# 20241126.net
KiCad netlist of a schematic drawn in Altium Designer
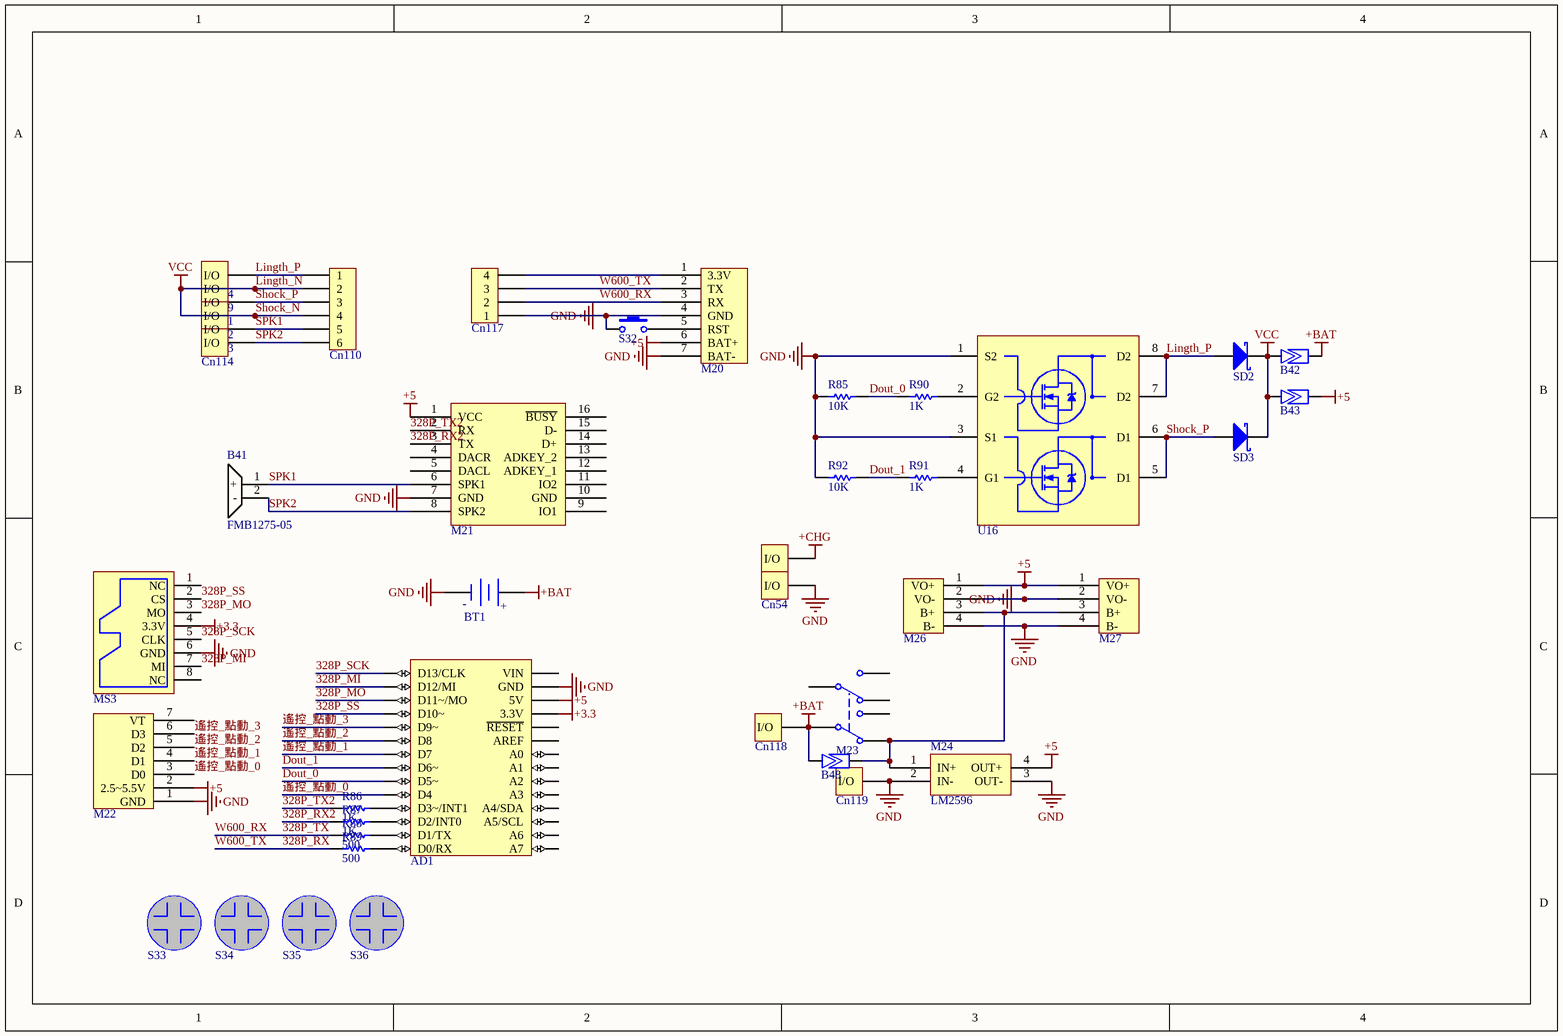
[diagram p0: 松菸_幻影光靈_屍禁_提燈_20241126.SchDoc]

(export (version "E")
  (design (tool "Eeschema 10.0.6"))
  (components
    (comp (ref "AD1")
      (value "Arduino NANO")
      (footprint "Arduino NANO")
      (description "單晶片")
      (libsource (lib "MyLibray") (part "Arduino NANO"))
    )
    (comp (ref "B41")
      (value "FMB1275-05")
      (footprint "Buzzer_12085")
      (description "無源蜂鳴器")
      (libsource (lib "MyLibray") (part "Buzzer"))
    )
    (comp (ref "B42")
      (value "短路")
      (footprint "BYPASS-0805")
      (description "短路焊點(如標註短路則需額外補錫使其短路)")
      (libsource (lib "MyLibray") (part "Bypass"))
    )
    (comp (ref "B43")
      (value "短路")
      (footprint "BYPASS-0805")
      (description "短路焊點(如標註短路則需額外補錫使其短路)")
      (libsource (lib "MyLibray") (part "Bypass"))
    )
    (comp (ref "B48")
      (value "短路")
      (footprint "BYPASS-1206")
      (description "短路焊點(如標註短路則需額外補錫使其短路)")
      (libsource (lib "MyLibray") (part "Bypass"))
    )
    (comp (ref "BT1")
      (value "18650")
      (footprint "Battery_18650")
      (description "電池")
      (libsource (lib "MyLibray") (part "Battery"))
    )
    (comp (ref "Cn53")
      (value "Contact")
      (footprint "Conntact_Stamp hole_0.6\"")
      (description "接線端子、接點、郵票孔(非焊接元件)")
      (libsource (lib "MyLibray") (part "Conntact"))
    )
    (comp (ref "Cn54")
      (value "Contact")
      (footprint "Conntact_Stamp hole_0.6\"")
      (description "接線端子、接點、郵票孔(非焊接元件)")
      (libsource (lib "MyLibray") (part "Conntact"))
    )
    (comp (ref "Cn104")
      (value "Contact")
      (footprint "Conntact_Stamp hole_0.6\"")
      (description "接線端子、接點、郵票孔(非焊接元件)")
      (libsource (lib "MyLibray") (part "Conntact"))
    )
    (comp (ref "Cn109")
      (value "Contact")
      (footprint "Conntact_Stamp hole_0.6\"")
      (description "接線端子、接點、郵票孔(非焊接元件)")
      (libsource (lib "") (part "Conntact_1"))
    )
    (comp (ref "Cn110")
      (value "KF2510-6")
      (footprint "Connector_KF2510-6A")
      (description "連接器")
      (libsource (lib "MyLibray") (part "Conntact(6P)"))
    )
    (comp (ref "Cn111")
      (value "Contact")
      (footprint "Conntact_Stamp hole_0.6\"")
      (description "接線端子、接點、郵票孔(非焊接元件)")
      (libsource (lib "MyLibray") (part "Conntact"))
    )
    (comp (ref "Cn112")
      (value "Contact")
      (footprint "Conntact_Stamp hole_0.6\"")
      (description "接線端子、接點、郵票孔(非焊接元件)")
      (libsource (lib "MyLibray") (part "Conntact"))
    )
    (comp (ref "Cn113")
      (value "Contact")
      (footprint "Conntact_Stamp hole_0.6\"")
      (description "接線端子、接點、郵票孔(非焊接元件)")
      (libsource (lib "MyLibray") (part "Conntact"))
    )
    (comp (ref "Cn114")
      (value "Contact")
      (footprint "Conntact_Stamp hole_0.6\"")
      (description "接線端子、接點、郵票孔(非焊接元件)")
      (libsource (lib "MyLibray") (part "Conntact"))
    )
    (comp (ref "Cn117")
      (value "KF2510-4")
      (footprint "Connector_KF2510-4A")
      (description "連接器")
      (libsource (lib "MyLibray") (part "Conntact(4P)"))
    )
    (comp (ref "Cn118")
      (value "Contact")
      (footprint "Conntact_Stamp hole_0.6\"")
      (description "接線端子、接點、郵票孔(非焊接元件)")
      (libsource (lib "MyLibray") (part "Conntact"))
    )
    (comp (ref "Cn119")
      (value "Contact")
      (footprint "Conntact_Stamp hole_0.6\"")
      (description "接線端子、接點、郵票孔(非焊接元件)")
      (libsource (lib "MyLibray") (part "Conntact"))
    )
    (comp (ref "M20")
      (value "HH_W600_V2.0")
      (footprint "HH_W600_V2.0")
      (libsource (lib "MyLibray") (part "HH_W600_V2.0"))
    )
    (comp (ref "M21")
      (value "mp3-tf-16p")
      (footprint "BY8001-16P")
      (description "TTL通訊SD卡撥放mp3模組")
      (libsource (lib "MyLibray") (part "Mini MP3 Player"))
    )
    (comp (ref "M22")
      (value "XR390")
      (footprint "XR390 Module")
      (description "遙控器模組")
      (libsource (lib "MyLibray") (part "XR390"))
    )
    (comp (ref "M23")
      (value "MST22D18G2")
      (footprint "Switch_MST22D18G2")
      (description "開關_滑動_2通道")
      (libsource (lib "MyLibray") (part "Switch_Slide_2"))
    )
    (comp (ref "M24")
      (value "LM2596")
      (footprint "LM2596 Module")
      (description "DC to DC 降壓模組")
      (libsource (lib "MyLibray") (part "LM2596_Moduld"))
    )
    (comp (ref "M26")
      (value "4056+LN2220PAR_Module")
      (footprint "4056+LN2220PAR_Moduld")
      (description "鋰電池充電升壓模組")
      (libsource (lib "MyLibray") (part "4056+LN2220PAR_Module"))
    )
    (comp (ref "M27")
      (value "4056+LN2220PAR_Module")
      (footprint "4056+LN2220PAR_Moduld")
      (description "鋰電池充電升壓模組")
      (libsource (lib "") (part "4056+LN2220PAR_Module_1"))
    )
    (comp (ref "MS3")
      (value "Interface_MicroSD card slot")
      (footprint "Interface_MicroSD card slot")
      (description "Micro SD 卡座")
      (libsource (lib "MyLibray") (part "Interface_MicroSD card slot"))
    )
    (comp (ref "R85")
      (value "10K")
      (footprint "Res-1206")
      (description "電阻")
      (libsource (lib "MyLibray") (part "Res"))
    )
    (comp (ref "R86")
      (value "1K")
      (footprint "Res-1206")
      (description "電阻")
      (libsource (lib "MyLibray") (part "Res"))
    )
    (comp (ref "R87")
      (value "1K")
      (footprint "Res-1206")
      (description "電阻")
      (libsource (lib "MyLibray") (part "Res"))
    )
    (comp (ref "R88")
      (value "500")
      (footprint "Res-1206")
      (description "電阻")
      (libsource (lib "MyLibray") (part "Res"))
    )
    (comp (ref "R89")
      (value "500")
      (footprint "Res-1206")
      (description "電阻")
      (libsource (lib "MyLibray") (part "Res"))
    )
    (comp (ref "R90")
      (value "1K")
      (footprint "Res-1206")
      (description "電阻")
      (libsource (lib "MyLibray") (part "Res"))
    )
    (comp (ref "R91")
      (value "1K")
      (footprint "Res-1206")
      (description "電阻")
      (libsource (lib "MyLibray") (part "Res"))
    )
    (comp (ref "R92")
      (value "10K")
      (footprint "Res-1206")
      (description "電阻")
      (libsource (lib "MyLibray") (part "Res"))
    )
    (comp (ref "S32")
      (value "Switch")
      (footprint "Switch SMD-3.6*6*2.5")
      (description "開關_按鍵")
      (libsource (lib "MyLibray") (part "Switch"))
    )
    (comp (ref "S33")
      (value "M3")
      (footprint "Screw M3")
      (description "螺絲(非焊接元件)")
      (libsource (lib "MyLibray") (part "Screw"))
    )
    (comp (ref "S34")
      (value "M3")
      (footprint "Screw M3")
      (description "螺絲(非焊接元件)")
      (libsource (lib "MyLibray") (part "Screw"))
    )
    (comp (ref "S35")
      (value "M3")
      (footprint "Screw M3")
      (description "螺絲(非焊接元件)")
      (libsource (lib "MyLibray") (part "Screw"))
    )
    (comp (ref "S36")
      (value "M3")
      (footprint "Screw M3")
      (description "螺絲(非焊接元件)")
      (libsource (lib "MyLibray") (part "Screw"))
    )
    (comp (ref "SD2")
      (value "SS56")
      (footprint "Diode_SMA")
      (description "二極體_蕭特基")
      (libsource (lib "MyLibray") (part "Diode_Schottky"))
    )
    (comp (ref "SD3")
      (value "SS56")
      (footprint "Diode_SMA")
      (description "二極體_蕭特基")
      (libsource (lib "MyLibray") (part "Diode_Schottky"))
    )
    (comp (ref "U16")
      (value "AO4800")
      (footprint "SOP-8")
      (description "MOS,雙NMOS")
      (libsource (lib "MyLibray") (part "MOS_Dual N_AO4800"))
    )
  )
  (nets
    (net (code "1") (name "+3.3") (class "Default")
      (node (ref "AD1") (pin "5") (pinfunction "3.3V_5") (pintype "passive"))
      (node (ref "MS3") (pin "4") (pinfunction "3.3V_4") (pintype "power_in"))
    )
    (net (code "2") (name "+5") (class "Default")
      (node (ref "AD1") (pin "3") (pinfunction "5V_3") (pintype "passive"))
      (node (ref "B43") (pin "1") (pinfunction "1_1") (pintype "passive"))
      (node (ref "M20") (pin "6") (pinfunction "BAT+_6") (pintype "passive"))
      (node (ref "M21") (pin "1") (pinfunction "VCC_1") (pintype "passive"))
      (node (ref "M22") (pin "2") (pinfunction "2.5~5.5V_2") (pintype "passive"))
      (node (ref "M24") (pin "4") (pinfunction "OUT+_4") (pintype "passive"))
      (node (ref "M26") (pin "1") (pinfunction "VO+_1") (pintype "passive"))
      (node (ref "M27") (pin "1") (pinfunction "VO+_1") (pintype "passive"))
    )
    (net (code "3") (name "+BAT") (class "Default")
      (node (ref "B42") (pin "1") (pinfunction "1_1") (pintype "passive"))
      (node (ref "B48") (pin "2") (pinfunction "2_2") (pintype "passive"))
      (node (ref "BT1") (pin "1") (pinfunction "+_1") (pintype "power_in"))
      (node (ref "Cn118") (pin "1") (pinfunction "I/O_1") (pintype "passive"))
      (node (ref "M23") (pin "1") (pinfunction "1_1") (pintype "passive"))
    )
    (net (code "4") (name "+CHG") (class "Default")
      (node (ref "Cn53") (pin "1") (pinfunction "I/O_1") (pintype "passive"))
    )
    (net (code "5") (name "/328P_MI") (class "Default")
      (node (ref "AD1") (pin "19") (pinfunction "D12/MI_19") (pintype "bidirectional"))
      (node (ref "MS3") (pin "7") (pinfunction "MI_7") (pintype "passive"))
    )
    (net (code "6") (name "/328P_MO") (class "Default")
      (node (ref "AD1") (pin "18") (pinfunction "D11~/MO_18") (pintype "bidirectional"))
      (node (ref "MS3") (pin "3") (pinfunction "MO_3") (pintype "passive"))
    )
    (net (code "7") (name "/328P_RX") (class "Default")
      (node (ref "Cn117") (pin "3") (pinfunction "3_3") (pintype "passive"))
      (node (ref "M20") (pin "2") (pinfunction "TX_2") (pintype "passive"))
      (node (ref "R89") (pin "1") (pinfunction "1_1") (pintype "passive"))
    )
    (net (code "8") (name "/328P_RX2") (class "Default")
      (node (ref "M21") (pin "3") (pinfunction "TX_3") (pintype "passive"))
      (node (ref "R87") (pin "1") (pinfunction "1_1") (pintype "passive"))
    )
    (net (code "9") (name "/328P_SCK") (class "Default")
      (node (ref "AD1") (pin "20") (pinfunction "D13/CLK_20") (pintype "bidirectional"))
      (node (ref "MS3") (pin "5") (pinfunction "CLK_5") (pintype "passive"))
    )
    (net (code "10") (name "/328P_SS") (class "Default")
      (node (ref "AD1") (pin "17") (pinfunction "D10~_17") (pintype "bidirectional"))
      (node (ref "MS3") (pin "2") (pinfunction "CS_2") (pintype "passive"))
    )
    (net (code "11") (name "/328P_TX") (class "Default")
      (node (ref "Cn117") (pin "2") (pinfunction "2_2") (pintype "passive"))
      (node (ref "M20") (pin "3") (pinfunction "RX_3") (pintype "passive"))
      (node (ref "R88") (pin "1") (pinfunction "1_1") (pintype "passive"))
    )
    (net (code "12") (name "/328P_TX2") (class "Default")
      (node (ref "M21") (pin "2") (pinfunction "RX_2") (pintype "passive"))
      (node (ref "R86") (pin "1") (pinfunction "1_1") (pintype "passive"))
    )
    (net (code "13") (name "/Dout_0") (class "Default")
      (node (ref "AD1") (pin "12") (pinfunction "D5~_12") (pintype "bidirectional"))
      (node (ref "R85") (pin "2") (pinfunction "2_2") (pintype "passive"))
      (node (ref "R90") (pin "1") (pinfunction "1_1") (pintype "passive"))
    )
    (net (code "14") (name "/Dout_1") (class "Default")
      (node (ref "AD1") (pin "13") (pinfunction "D6~_13") (pintype "bidirectional"))
      (node (ref "R91") (pin "1") (pinfunction "1_1") (pintype "passive"))
      (node (ref "R92") (pin "2") (pinfunction "2_2") (pintype "passive"))
    )
    (net (code "15") (name "/Lingth_P") (class "Default")
      (node (ref "Cn104") (pin "1") (pinfunction "I/O_1") (pintype "passive"))
      (node (ref "Cn110") (pin "1") (pinfunction "1_1") (pintype "passive"))
      (node (ref "SD2") (pin "2") (pinfunction "A_2") (pintype "passive"))
      (node (ref "U16") (pin "7") (pinfunction "D2_7") (pintype "passive"))
      (node (ref "U16") (pin "8") (pinfunction "D2_8") (pintype "passive"))
    )
    (net (code "16") (name "/SPK1") (class "Default")
      (node (ref "B41") (pin "1") (pinfunction "+_1") (pintype "passive"))
      (node (ref "Cn110") (pin "5") (pinfunction "5_5") (pintype "passive"))
      (node (ref "Cn113") (pin "1") (pinfunction "I/O_1") (pintype "passive"))
      (node (ref "M21") (pin "6") (pinfunction "SPK1_6") (pintype "passive"))
    )
    (net (code "17") (name "/SPK2") (class "Default")
      (node (ref "B41") (pin "2") (pinfunction "-_2") (pintype "passive"))
      (node (ref "Cn110") (pin "6") (pinfunction "6_6") (pintype "passive"))
      (node (ref "Cn114") (pin "1") (pinfunction "I/O_1") (pintype "passive"))
      (node (ref "M21") (pin "8") (pinfunction "SPK2_8") (pintype "passive"))
    )
    (net (code "18") (name "/Shock_P") (class "Default")
      (node (ref "Cn110") (pin "3") (pinfunction "3_3") (pintype "passive"))
      (node (ref "Cn111") (pin "1") (pinfunction "I/O_1") (pintype "passive"))
      (node (ref "SD3") (pin "2") (pinfunction "A_2") (pintype "passive"))
      (node (ref "U16") (pin "5") (pinfunction "D1_5") (pintype "passive"))
      (node (ref "U16") (pin "6") (pinfunction "D1_6") (pintype "passive"))
    )
    (net (code "19") (name "/遙控_點動_0") (class "Default")
      (node (ref "AD1") (pin "11") (pinfunction "D4_11") (pintype "bidirectional"))
      (node (ref "M22") (pin "3") (pinfunction "D0_3") (pintype "passive"))
    )
    (net (code "20") (name "/遙控_點動_1") (class "Default")
      (node (ref "AD1") (pin "14") (pinfunction "D7_14") (pintype "bidirectional"))
      (node (ref "M22") (pin "4") (pinfunction "D1_4") (pintype "passive"))
    )
    (net (code "21") (name "/遙控_點動_2") (class "Default")
      (node (ref "AD1") (pin "15") (pinfunction "D8_15") (pintype "bidirectional"))
      (node (ref "M22") (pin "5") (pinfunction "D2_5") (pintype "passive"))
    )
    (net (code "22") (name "/遙控_點動_3") (class "Default")
      (node (ref "AD1") (pin "16") (pinfunction "D9~_16") (pintype "bidirectional"))
      (node (ref "M22") (pin "6") (pinfunction "D3_6") (pintype "passive"))
    )
    (net (code "23") (name "GND") (class "Default")
      (node (ref "AD1") (pin "2") (pinfunction "GND_2") (pintype "passive"))
      (node (ref "BT1") (pin "2") (pinfunction "-_2") (pintype "power_in"))
      (node (ref "Cn117") (pin "1") (pinfunction "1_1") (pintype "passive"))
      (node (ref "Cn119") (pin "1") (pinfunction "I/O_1") (pintype "passive"))
      (node (ref "Cn54") (pin "1") (pinfunction "I/O_1") (pintype "passive"))
      (node (ref "M20") (pin "4") (pinfunction "GND_4") (pintype "passive"))
      (node (ref "M20") (pin "7") (pinfunction "BAT-_7") (pintype "passive"))
      (node (ref "M21") (pin "7") (pinfunction "GND_7") (pintype "passive"))
      (node (ref "M22") (pin "1") (pinfunction "GND_1") (pintype "passive"))
      (node (ref "M24") (pin "2") (pinfunction "IN-_2") (pintype "passive"))
      (node (ref "M24") (pin "3") (pinfunction "OUT-_3") (pintype "passive"))
      (node (ref "M26") (pin "2") (pinfunction "VO-_2") (pintype "passive"))
      (node (ref "M26") (pin "4") (pinfunction "B-_4") (pintype "passive"))
      (node (ref "M27") (pin "2") (pinfunction "VO-_2") (pintype "passive"))
      (node (ref "M27") (pin "4") (pinfunction "B-_4") (pintype "passive"))
      (node (ref "MS3") (pin "6") (pinfunction "GND_6") (pintype "power_in"))
      (node (ref "R85") (pin "1") (pinfunction "1_1") (pintype "passive"))
      (node (ref "R92") (pin "1") (pinfunction "1_1") (pintype "passive"))
      (node (ref "S32") (pin "1") (pinfunction "1_1") (pintype "passive"))
      (node (ref "U16") (pin "1") (pinfunction "S2_1") (pintype "passive"))
      (node (ref "U16") (pin "3") (pinfunction "S1_3") (pintype "passive"))
    )
    (net (code "24") (name "Net-(AD1-D0{slash}RX)") (class "Default")
      (node (ref "AD1") (pin "7") (pinfunction "D0/RX_7") (pintype "bidirectional"))
      (node (ref "R89") (pin "2") (pinfunction "2_2") (pintype "passive"))
    )
    (net (code "25") (name "Net-(AD1-D1{slash}TX)") (class "Default")
      (node (ref "AD1") (pin "8") (pinfunction "D1/TX_8") (pintype "bidirectional"))
      (node (ref "R88") (pin "2") (pinfunction "2_2") (pintype "passive"))
    )
    (net (code "26") (name "Net-(AD1-D2{slash}INT0)") (class "Default")
      (node (ref "AD1") (pin "9") (pinfunction "D2/INT0_9") (pintype "bidirectional"))
      (node (ref "R87") (pin "2") (pinfunction "2_2") (pintype "passive"))
    )
    (net (code "27") (name "Net-(AD1-D3~{slash}INT1)") (class "Default")
      (node (ref "AD1") (pin "10") (pinfunction "D3~/INT1_10") (pintype "bidirectional"))
      (node (ref "R86") (pin "2") (pinfunction "2_2") (pintype "passive"))
    )
    (net (code "28") (name "Net-(M20-3.3V)") (class "Default")
      (node (ref "Cn117") (pin "4") (pinfunction "4_4") (pintype "passive"))
      (node (ref "M20") (pin "1") (pinfunction "3.3V_1") (pintype "passive"))
    )
    (net (code "29") (name "Net-(M20-RST)") (class "Default")
      (node (ref "M20") (pin "5") (pinfunction "RST_5") (pintype "passive"))
      (node (ref "S32") (pin "2") (pinfunction "2_2") (pintype "passive"))
    )
    (net (code "30") (name "Net-(M24-IN+)") (class "Default")
      (node (ref "B48") (pin "1") (pinfunction "1_1") (pintype "passive"))
      (node (ref "M23") (pin "2") (pinfunction "2_2") (pintype "passive"))
      (node (ref "M24") (pin "1") (pinfunction "IN+_1") (pintype "passive"))
      (node (ref "M26") (pin "3") (pinfunction "B+_3") (pintype "passive"))
      (node (ref "M27") (pin "3") (pinfunction "B+_3") (pintype "passive"))
    )
    (net (code "31") (name "Net-(U16-G1)") (class "Default")
      (node (ref "R91") (pin "2") (pinfunction "2_2") (pintype "passive"))
      (node (ref "U16") (pin "4") (pinfunction "G1_4") (pintype "passive"))
    )
    (net (code "32") (name "Net-(U16-G2)") (class "Default")
      (node (ref "R90") (pin "2") (pinfunction "2_2") (pintype "passive"))
      (node (ref "U16") (pin "2") (pinfunction "G2_2") (pintype "passive"))
    )
    (net (code "33") (name "VCC") (class "Default")
      (node (ref "B42") (pin "2") (pinfunction "2_2") (pintype "passive"))
      (node (ref "B43") (pin "2") (pinfunction "2_2") (pintype "passive"))
      (node (ref "Cn109") (pin "1") (pinfunction "I/O_1") (pintype "passive"))
      (node (ref "Cn110") (pin "2") (pinfunction "2_2") (pintype "passive"))
      (node (ref "Cn110") (pin "4") (pinfunction "4_4") (pintype "passive"))
      (node (ref "Cn112") (pin "1") (pinfunction "I/O_1") (pintype "passive"))
      (node (ref "SD2") (pin "1") (pinfunction "K_1") (pintype "passive"))
      (node (ref "SD3") (pin "1") (pinfunction "K_1") (pintype "passive"))
    )
    (net (code "34") (name "unconnected-(AD1-A0-Pad21)") (class "Default")
      (node (ref "AD1") (pin "21") (pinfunction "A0_21") (pintype "bidirectional"))
    )
    (net (code "35") (name "unconnected-(AD1-A1-Pad22)") (class "Default")
      (node (ref "AD1") (pin "22") (pinfunction "A1_22") (pintype "bidirectional"))
    )
    (net (code "36") (name "unconnected-(AD1-A2-Pad23)") (class "Default")
      (node (ref "AD1") (pin "23") (pinfunction "A2_23") (pintype "bidirectional"))
    )
    (net (code "37") (name "unconnected-(AD1-A3-Pad24)") (class "Default")
      (node (ref "AD1") (pin "24") (pinfunction "A3_24") (pintype "bidirectional"))
    )
    (net (code "38") (name "unconnected-(AD1-A4{slash}SDA-Pad25)") (class "Default")
      (node (ref "AD1") (pin "25") (pinfunction "A4/SDA_25") (pintype "bidirectional"))
    )
    (net (code "39") (name "unconnected-(AD1-A5{slash}SCL-Pad26)") (class "Default")
      (node (ref "AD1") (pin "26") (pinfunction "A5/SCL_26") (pintype "bidirectional"))
    )
    (net (code "40") (name "unconnected-(AD1-A6-Pad27)") (class "Default")
      (node (ref "AD1") (pin "27") (pinfunction "A6_27") (pintype "bidirectional"))
    )
    (net (code "41") (name "unconnected-(AD1-A7-Pad28)") (class "Default")
      (node (ref "AD1") (pin "28") (pinfunction "A7_28") (pintype "bidirectional"))
    )
    (net (code "42") (name "unconnected-(AD1-AREF-Pad6)") (class "Default")
      (node (ref "AD1") (pin "6") (pinfunction "AREF_6") (pintype "passive"))
    )
    (net (code "43") (name "unconnected-(AD1-VIN-Pad1)") (class "Default")
      (node (ref "AD1") (pin "1") (pinfunction "VIN_1") (pintype "passive"))
    )
    (net (code "44") (name "unconnected-(AD1-~{RESET}-Pad4)") (class "Default")
      (node (ref "AD1") (pin "4") (pinfunction "~{RESET}_4") (pintype "passive"))
    )
    (net (code "45") (name "unconnected-(M21-ADKEY_1-Pad12)") (class "Default")
      (node (ref "M21") (pin "12") (pinfunction "ADKEY_1_12") (pintype "passive"))
    )
    (net (code "46") (name "unconnected-(M21-ADKEY_2-Pad13)") (class "Default")
      (node (ref "M21") (pin "13") (pinfunction "ADKEY_2_13") (pintype "passive"))
    )
    (net (code "47") (name "unconnected-(M21-D+-Pad14)") (class "Default")
      (node (ref "M21") (pin "14") (pinfunction "D+_14") (pintype "passive"))
    )
    (net (code "48") (name "unconnected-(M21-D--Pad15)") (class "Default")
      (node (ref "M21") (pin "15") (pinfunction "D-_15") (pintype "passive"))
    )
    (net (code "49") (name "unconnected-(M21-DACL-Pad5)") (class "Default")
      (node (ref "M21") (pin "5") (pinfunction "DACL_5") (pintype "passive"))
    )
    (net (code "50") (name "unconnected-(M21-DACR-Pad4)") (class "Default")
      (node (ref "M21") (pin "4") (pinfunction "DACR_4") (pintype "passive"))
    )
    (net (code "51") (name "unconnected-(M21-GND-Pad10)") (class "Default")
      (node (ref "M21") (pin "10") (pinfunction "GND_10") (pintype "passive"))
    )
    (net (code "52") (name "unconnected-(M21-IO1-Pad9)") (class "Default")
      (node (ref "M21") (pin "9") (pinfunction "IO1_9") (pintype "passive"))
    )
    (net (code "53") (name "unconnected-(M21-IO2-Pad11)") (class "Default")
      (node (ref "M21") (pin "11") (pinfunction "IO2_11") (pintype "passive"))
    )
    (net (code "54") (name "unconnected-(M21-~{BUSY}-Pad16)") (class "Default")
      (node (ref "M21") (pin "16") (pinfunction "~{BUSY}_16") (pintype "passive"))
    )
    (net (code "55") (name "unconnected-(M22-VT-Pad7)") (class "Default")
      (node (ref "M22") (pin "7") (pinfunction "VT_7") (pintype "passive"))
    )
    (net (code "56") (name "unconnected-(M23-Pad3)") (class "Default")
      (node (ref "M23") (pin "3") (pinfunction "3_3") (pintype "passive"))
    )
    (net (code "57") (name "unconnected-(M23-Pad4)") (class "Default")
      (node (ref "M23") (pin "4") (pinfunction "4_4") (pintype "passive"))
    )
    (net (code "58") (name "unconnected-(M23-Pad5)") (class "Default")
      (node (ref "M23") (pin "5") (pinfunction "5_5") (pintype "passive"))
    )
    (net (code "59") (name "unconnected-(M23-Pad6)") (class "Default")
      (node (ref "M23") (pin "6") (pinfunction "6_6") (pintype "passive"))
    )
    (net (code "60") (name "unconnected-(MS3-NC-Pad1)") (class "Default")
      (node (ref "MS3") (pin "1") (pinfunction "NC_1") (pintype "passive"))
    )
    (net (code "61") (name "unconnected-(MS3-NC-Pad8)") (class "Default")
      (node (ref "MS3") (pin "8") (pinfunction "NC_8") (pintype "passive"))
    )
  )
)
